# nixie_board.net
KiCad netlist of a schematic drawn in Altium Designer
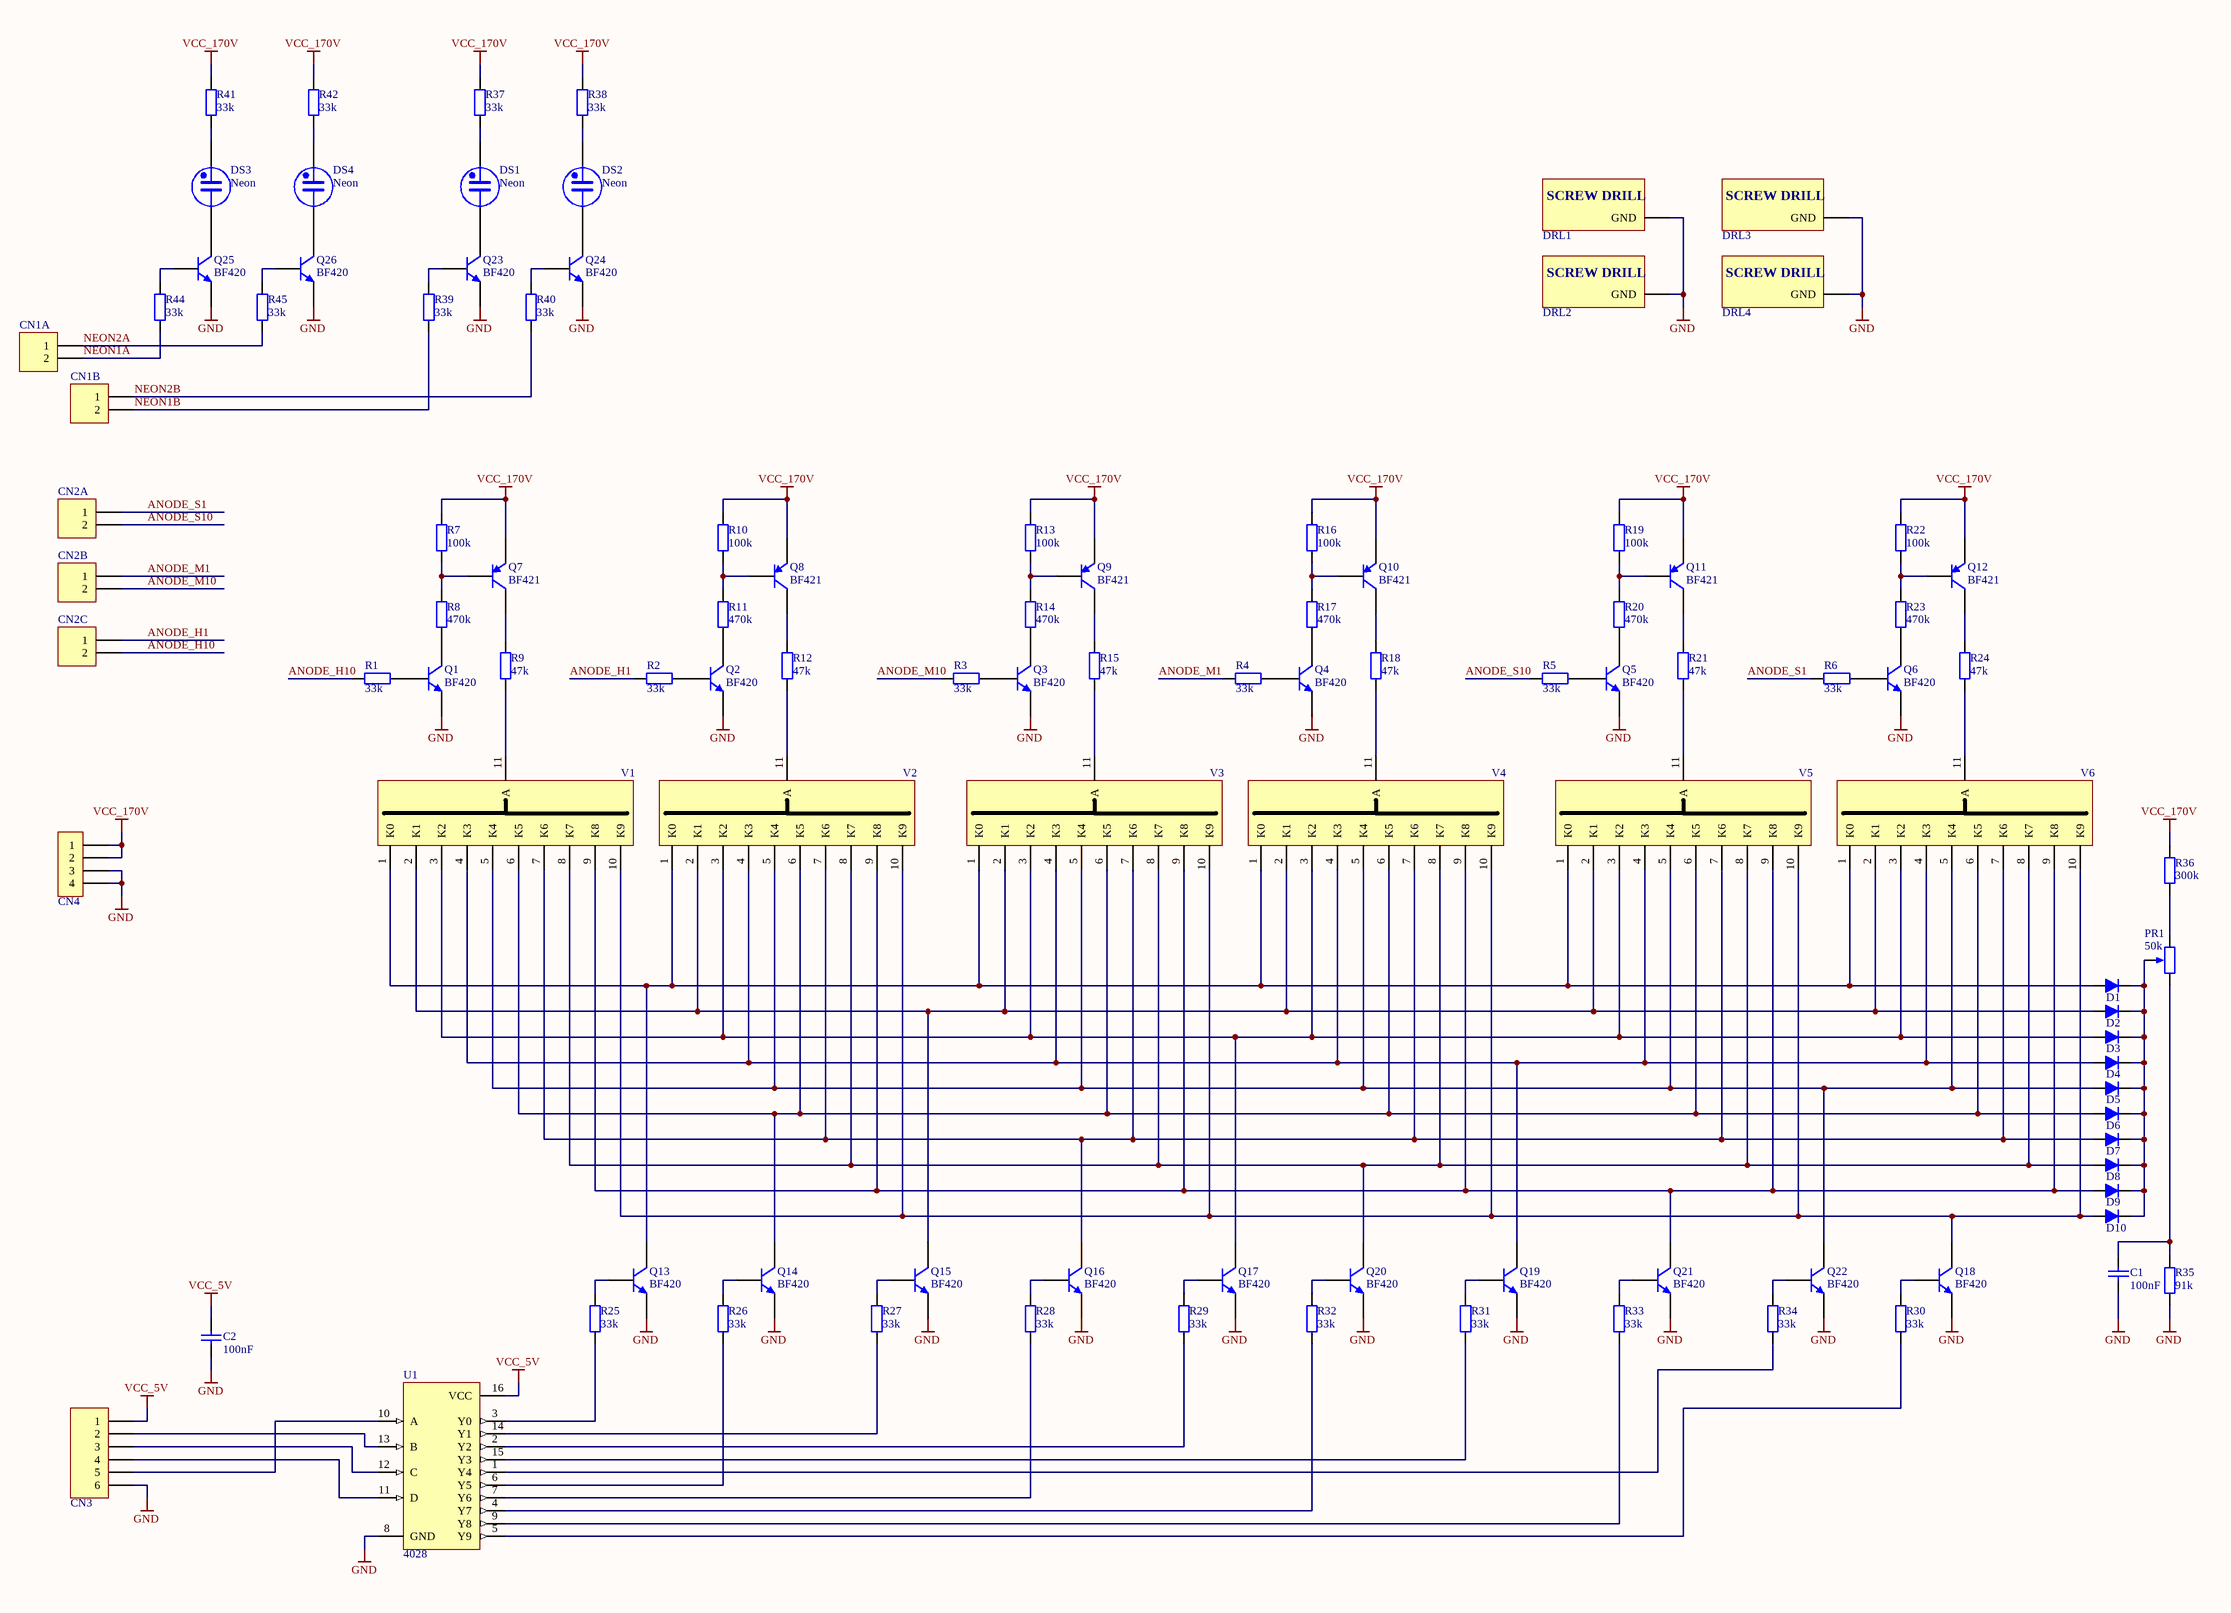
[diagram p0: nixie_board.SCHDOC]

(export (version "E")
  (design (tool "Eeschema 10.0.6"))
  (components
    (comp (ref "C1")
      (value "100nF")
      (footprint "C-RM5")
      (description "Capacitor")
      (libsource (lib "main_lib") (part "Cap"))
    )
    (comp (ref "C2")
      (value "100nF")
      (footprint "C-RM5")
      (description "Capacitor")
      (libsource (lib "main_lib") (part "Cap"))
    )
    (comp (ref "CN1A")
      (value "~")
      (footprint "GP2x1_maual")
      (description "Goldpin, 2-Pin")
      (libsource (lib "main_lib_sch") (part "GP 2X1"))
    )
    (comp (ref "CN1B")
      (value "~")
      (footprint "GP2x1_maual")
      (description "Goldpin, 2-Pin")
      (libsource (lib "main_lib_sch") (part "GP 2X1"))
    )
    (comp (ref "CN2A")
      (value "~")
      (footprint "GP2x1_maual")
      (description "Goldpin, 2-Pin")
      (libsource (lib "main_lib_sch") (part "GP 2X1"))
    )
    (comp (ref "CN2B")
      (value "~")
      (footprint "GP2x1_maual")
      (description "Goldpin, 2-Pin")
      (libsource (lib "main_lib_sch") (part "GP 2X1"))
    )
    (comp (ref "CN2C")
      (value "~")
      (footprint "GP2x1_maual")
      (description "Goldpin, 2-Pin")
      (libsource (lib "main_lib_sch") (part "GP 2X1"))
    )
    (comp (ref "CN3")
      (value "GP 6X1")
      (footprint "GP6x1_manual")
      (description "Gold Pin, 6-Pin")
      (libsource (lib "main_lib") (part "GP 6X1"))
    )
    (comp (ref "CN4")
      (value "~")
      (footprint "GP4x1_MANUAL")
      (description "Gold Pin, 4-Pin")
      (libsource (lib "main_lib_sch") (part "GP 4X1"))
    )
    (comp (ref "D1")
      (value "~")
      (footprint "DO35_LONG")
      (description "Fast rectifier diode: 250V 0.25A, <50ns DO35")
      (libsource (lib "main_lib_sch") (part "BAVP21"))
    )
    (comp (ref "D2")
      (value "~")
      (footprint "DO35_LONG")
      (description "Fast rectifier diode: 250V 0.25A, <50ns DO35")
      (libsource (lib "main_lib_sch") (part "BAVP21"))
    )
    (comp (ref "D3")
      (value "~")
      (footprint "DO35_LONG")
      (description "Fast rectifier diode: 250V 0.25A, <50ns DO35")
      (libsource (lib "main_lib_sch") (part "BAVP21"))
    )
    (comp (ref "D4")
      (value "~")
      (footprint "DO35_LONG")
      (description "Fast rectifier diode: 250V 0.25A, <50ns DO35")
      (libsource (lib "main_lib_sch") (part "BAVP21"))
    )
    (comp (ref "D5")
      (value "~")
      (footprint "DO35_LONG")
      (description "Fast rectifier diode: 250V 0.25A, <50ns DO35")
      (libsource (lib "main_lib_sch") (part "BAVP21"))
    )
    (comp (ref "D6")
      (value "~")
      (footprint "DO35_LONG")
      (description "Fast rectifier diode: 250V 0.25A, <50ns DO35")
      (libsource (lib "main_lib_sch") (part "BAVP21"))
    )
    (comp (ref "D7")
      (value "~")
      (footprint "DO35_LONG")
      (description "Fast rectifier diode: 250V 0.25A, <50ns DO35")
      (libsource (lib "main_lib_sch") (part "BAVP21"))
    )
    (comp (ref "D8")
      (value "~")
      (footprint "DO35_LONG")
      (description "Fast rectifier diode: 250V 0.25A, <50ns DO35")
      (libsource (lib "main_lib_sch") (part "BAVP21"))
    )
    (comp (ref "D9")
      (value "~")
      (footprint "DO35_LONG")
      (description "Fast rectifier diode: 250V 0.25A, <50ns DO35")
      (libsource (lib "main_lib_sch") (part "BAVP21"))
    )
    (comp (ref "D10")
      (value "~")
      (footprint "DO35_LONG")
      (description "Fast rectifier diode: 250V 0.25A, <50ns DO35")
      (libsource (lib "main_lib_sch") (part "BAVP21"))
    )
    (comp (ref "DRL1")
      (value "SCREW DRILL")
      (footprint "3mm screw drill I")
      (description "Screw Drill")
      (libsource (lib "main_lib") (part "SCREW DRILL"))
    )
    (comp (ref "DRL2")
      (value "SCREW DRILL")
      (footprint "3mm screw drill I")
      (description "Screw Drill")
      (libsource (lib "main_lib") (part "SCREW DRILL"))
    )
    (comp (ref "DRL3")
      (value "SCREW DRILL")
      (footprint "3mm screw drill I")
      (description "Screw Drill")
      (libsource (lib "main_lib") (part "SCREW DRILL"))
    )
    (comp (ref "DRL4")
      (value "SCREW DRILL")
      (footprint "3mm screw drill I")
      (description "Screw Drill")
      (libsource (lib "main_lib") (part "SCREW DRILL"))
    )
    (comp (ref "DS1")
      (value "Neon")
      (footprint "NEON_6mm")
      (description "Neon Bulb")
      (fields (field (name "PUBLISHER") "Altium Limited"))
      (libsource (lib "main_lib") (part "Neon"))
    )
    (comp (ref "DS2")
      (value "Neon")
      (footprint "NEON_6mm")
      (description "Neon Bulb")
      (fields (field (name "PUBLISHER") "Altium Limited"))
      (libsource (lib "main_lib") (part "Neon"))
    )
    (comp (ref "DS3")
      (value "Neon")
      (footprint "NEON_6mm")
      (description "Neon Bulb")
      (fields (field (name "PUBLISHER") "Altium Limited"))
      (libsource (lib "main_lib") (part "Neon"))
    )
    (comp (ref "DS4")
      (value "Neon")
      (footprint "NEON_6mm")
      (description "Neon Bulb")
      (fields (field (name "PUBLISHER") "Altium Limited"))
      (libsource (lib "main_lib") (part "Neon"))
    )
    (comp (ref "PR1")
      (value "50k")
      (footprint "CA6V")
      (description "Potentiometer")
      (libsource (lib "main_lib") (part "RPot"))
    )
    (comp (ref "Q1")
      (value "BF420")
      (footprint "TO-92")
      (description "NPN Transistor, 300V, 0.1A, 0.83W")
      (libsource (lib "main_lib_sch") (part "BF420"))
    )
    (comp (ref "Q2")
      (value "BF420")
      (footprint "TO-92")
      (description "NPN Transistor, 300V, 0.1A, 0.83W")
      (libsource (lib "main_lib_sch") (part "BF420"))
    )
    (comp (ref "Q3")
      (value "BF420")
      (footprint "TO-92")
      (description "NPN Transistor, 300V, 0.1A, 0.83W")
      (libsource (lib "main_lib_sch") (part "BF420"))
    )
    (comp (ref "Q4")
      (value "BF420")
      (footprint "TO-92")
      (description "NPN Transistor, 300V, 0.1A, 0.83W")
      (libsource (lib "main_lib_sch") (part "BF420"))
    )
    (comp (ref "Q5")
      (value "BF420")
      (footprint "TO-92")
      (description "NPN Transistor, 300V, 0.1A, 0.83W")
      (libsource (lib "main_lib_sch") (part "BF420"))
    )
    (comp (ref "Q6")
      (value "BF420")
      (footprint "TO-92")
      (description "NPN Transistor, 300V, 0.1A, 0.83W")
      (libsource (lib "main_lib_sch") (part "BF420"))
    )
    (comp (ref "Q7")
      (value "BF421")
      (footprint "TO-92")
      (description "PNP Transistor, 300V, 0.1A, 0.83W")
      (libsource (lib "main_lib_sch") (part "BF421"))
    )
    (comp (ref "Q8")
      (value "BF421")
      (footprint "TO-92")
      (description "PNP Transistor, 300V, 0.1A, 0.83W")
      (libsource (lib "main_lib_sch") (part "BF421"))
    )
    (comp (ref "Q9")
      (value "BF421")
      (footprint "TO-92")
      (description "PNP Transistor, 300V, 0.1A, 0.83W")
      (libsource (lib "main_lib_sch") (part "BF421"))
    )
    (comp (ref "Q10")
      (value "BF421")
      (footprint "TO-92")
      (description "PNP Transistor, 300V, 0.1A, 0.83W")
      (libsource (lib "main_lib_sch") (part "BF421"))
    )
    (comp (ref "Q11")
      (value "BF421")
      (footprint "TO-92")
      (description "PNP Transistor, 300V, 0.1A, 0.83W")
      (libsource (lib "main_lib_sch") (part "BF421"))
    )
    (comp (ref "Q12")
      (value "BF421")
      (footprint "TO-92")
      (description "PNP Transistor, 300V, 0.1A, 0.83W")
      (libsource (lib "main_lib_sch") (part "BF421"))
    )
    (comp (ref "Q13")
      (value "BF420")
      (footprint "TO-92")
      (description "NPN Transistor, 300V, 0.1A, 0.83W")
      (libsource (lib "main_lib_sch") (part "BF420"))
    )
    (comp (ref "Q14")
      (value "BF420")
      (footprint "TO-92")
      (description "NPN Transistor, 300V, 0.1A, 0.83W")
      (libsource (lib "main_lib_sch") (part "BF420"))
    )
    (comp (ref "Q15")
      (value "BF420")
      (footprint "TO-92")
      (description "NPN Transistor, 300V, 0.1A, 0.83W")
      (libsource (lib "main_lib_sch") (part "BF420"))
    )
    (comp (ref "Q16")
      (value "BF420")
      (footprint "TO-92")
      (description "NPN Transistor, 300V, 0.1A, 0.83W")
      (libsource (lib "main_lib_sch") (part "BF420"))
    )
    (comp (ref "Q17")
      (value "BF420")
      (footprint "TO-92")
      (description "NPN Transistor, 300V, 0.1A, 0.83W")
      (libsource (lib "main_lib_sch") (part "BF420"))
    )
    (comp (ref "Q18")
      (value "BF420")
      (footprint "TO-92")
      (description "NPN Transistor, 300V, 0.1A, 0.83W")
      (libsource (lib "main_lib_sch") (part "BF420"))
    )
    (comp (ref "Q19")
      (value "BF420")
      (footprint "TO-92")
      (description "NPN Transistor, 300V, 0.1A, 0.83W")
      (libsource (lib "main_lib_sch") (part "BF420"))
    )
    (comp (ref "Q20")
      (value "BF420")
      (footprint "TO-92")
      (description "NPN Transistor, 300V, 0.1A, 0.83W")
      (libsource (lib "main_lib_sch") (part "BF420"))
    )
    (comp (ref "Q21")
      (value "BF420")
      (footprint "TO-92")
      (description "NPN Transistor, 300V, 0.1A, 0.83W")
      (libsource (lib "main_lib_sch") (part "BF420"))
    )
    (comp (ref "Q22")
      (value "BF420")
      (footprint "TO-92")
      (description "NPN Transistor, 300V, 0.1A, 0.83W")
      (libsource (lib "main_lib_sch") (part "BF420"))
    )
    (comp (ref "Q23")
      (value "BF420")
      (footprint "TO-92")
      (description "NPN Transistor, 300V, 0.1A, 0.83W")
      (libsource (lib "main_lib_sch") (part "BF420"))
    )
    (comp (ref "Q24")
      (value "BF420")
      (footprint "TO-92")
      (description "NPN Transistor, 300V, 0.1A, 0.83W")
      (libsource (lib "main_lib_sch") (part "BF420"))
    )
    (comp (ref "Q25")
      (value "BF420")
      (footprint "TO-92")
      (description "NPN Transistor, 300V, 0.1A, 0.83W")
      (libsource (lib "main_lib_sch") (part "BF420"))
    )
    (comp (ref "Q26")
      (value "BF420")
      (footprint "TO-92")
      (description "NPN Transistor, 300V, 0.1A, 0.83W")
      (libsource (lib "main_lib_sch") (part "BF420"))
    )
    (comp (ref "R1")
      (value "33k")
      (footprint "R10-2")
      (description "Resistor")
      (libsource (lib "") (part "Res_2"))
    )
    (comp (ref "R2")
      (value "33k")
      (footprint "R10-2")
      (description "Resistor")
      (libsource (lib "") (part "Res_2"))
    )
    (comp (ref "R3")
      (value "33k")
      (footprint "R10-2")
      (description "Resistor")
      (libsource (lib "") (part "Res_2"))
    )
    (comp (ref "R4")
      (value "33k")
      (footprint "R10-2")
      (description "Resistor")
      (libsource (lib "") (part "Res_2"))
    )
    (comp (ref "R5")
      (value "33k")
      (footprint "R10-2")
      (description "Resistor")
      (libsource (lib "") (part "Res_2"))
    )
    (comp (ref "R6")
      (value "33k")
      (footprint "R10-2")
      (description "Resistor")
      (libsource (lib "") (part "Res_2"))
    )
    (comp (ref "R7")
      (value "100k")
      (footprint "R10-2")
      (description "Resistor")
      (libsource (lib "") (part "Res_1"))
    )
    (comp (ref "R8")
      (value "470k")
      (footprint "R10-2")
      (description "Resistor")
      (libsource (lib "") (part "Res_1"))
    )
    (comp (ref "R9")
      (value "47k")
      (footprint "R10-2")
      (description "Resistor")
      (libsource (lib "") (part "Res_1"))
    )
    (comp (ref "R10")
      (value "100k")
      (footprint "R10-2")
      (description "Resistor")
      (libsource (lib "") (part "Res_1"))
    )
    (comp (ref "R11")
      (value "470k")
      (footprint "R10-2")
      (description "Resistor")
      (libsource (lib "") (part "Res_1"))
    )
    (comp (ref "R12")
      (value "47k")
      (footprint "R10-2")
      (description "Resistor")
      (libsource (lib "") (part "Res_1"))
    )
    (comp (ref "R13")
      (value "100k")
      (footprint "R10-2")
      (description "Resistor")
      (libsource (lib "") (part "Res_1"))
    )
    (comp (ref "R14")
      (value "470k")
      (footprint "R10-2")
      (description "Resistor")
      (libsource (lib "") (part "Res_1"))
    )
    (comp (ref "R15")
      (value "47k")
      (footprint "R10-2")
      (description "Resistor")
      (libsource (lib "") (part "Res_1"))
    )
    (comp (ref "R16")
      (value "100k")
      (footprint "R10-2")
      (description "Resistor")
      (libsource (lib "") (part "Res_1"))
    )
    (comp (ref "R17")
      (value "470k")
      (footprint "R10-2")
      (description "Resistor")
      (libsource (lib "") (part "Res_1"))
    )
    (comp (ref "R18")
      (value "47k")
      (footprint "R10-2")
      (description "Resistor")
      (libsource (lib "") (part "Res_1"))
    )
    (comp (ref "R19")
      (value "100k")
      (footprint "R10-2")
      (description "Resistor")
      (libsource (lib "") (part "Res_1"))
    )
    (comp (ref "R20")
      (value "470k")
      (footprint "R10-2")
      (description "Resistor")
      (libsource (lib "") (part "Res_1"))
    )
    (comp (ref "R21")
      (value "47k")
      (footprint "R10-2")
      (description "Resistor")
      (libsource (lib "") (part "Res_1"))
    )
    (comp (ref "R22")
      (value "100k")
      (footprint "R10-2")
      (description "Resistor")
      (libsource (lib "") (part "Res_1"))
    )
    (comp (ref "R23")
      (value "470k")
      (footprint "R10-2")
      (description "Resistor")
      (libsource (lib "") (part "Res_1"))
    )
    (comp (ref "R24")
      (value "47k")
      (footprint "R10-2")
      (description "Resistor")
      (libsource (lib "") (part "Res_1"))
    )
    (comp (ref "R25")
      (value "33k")
      (footprint "R10-2")
      (description "Resistor")
      (libsource (lib "") (part "Res_1"))
    )
    (comp (ref "R26")
      (value "33k")
      (footprint "R10-2")
      (description "Resistor")
      (libsource (lib "") (part "Res_1"))
    )
    (comp (ref "R27")
      (value "33k")
      (footprint "R10-2")
      (description "Resistor")
      (libsource (lib "") (part "Res_1"))
    )
    (comp (ref "R28")
      (value "33k")
      (footprint "R10-2")
      (description "Resistor")
      (libsource (lib "") (part "Res_1"))
    )
    (comp (ref "R29")
      (value "33k")
      (footprint "R10-2")
      (description "Resistor")
      (libsource (lib "") (part "Res_1"))
    )
    (comp (ref "R30")
      (value "33k")
      (footprint "R10-2")
      (description "Resistor")
      (libsource (lib "") (part "Res_1"))
    )
    (comp (ref "R31")
      (value "33k")
      (footprint "R10-2")
      (description "Resistor")
      (libsource (lib "") (part "Res_1"))
    )
    (comp (ref "R32")
      (value "33k")
      (footprint "R10-2")
      (description "Resistor")
      (libsource (lib "") (part "Res_1"))
    )
    (comp (ref "R33")
      (value "33k")
      (footprint "R10-2")
      (description "Resistor")
      (libsource (lib "") (part "Res_1"))
    )
    (comp (ref "R34")
      (value "33k")
      (footprint "R10-2")
      (description "Resistor")
      (libsource (lib "") (part "Res_1"))
    )
    (comp (ref "R35")
      (value "91k")
      (footprint "R10-2")
      (description "Resistor")
      (libsource (lib "") (part "Res_1"))
    )
    (comp (ref "R36")
      (value "300k")
      (footprint "R10-2")
      (description "Resistor")
      (libsource (lib "") (part "Res_1"))
    )
    (comp (ref "R37")
      (value "33k")
      (footprint "R10-2")
      (description "Resistor")
      (libsource (lib "") (part "Res_1"))
    )
    (comp (ref "R38")
      (value "33k")
      (footprint "R10-2")
      (description "Resistor")
      (libsource (lib "") (part "Res_1"))
    )
    (comp (ref "R39")
      (value "33k")
      (footprint "R10-2")
      (description "Resistor")
      (libsource (lib "main_lib") (part "Res"))
    )
    (comp (ref "R40")
      (value "33k")
      (footprint "R10-2")
      (description "Resistor")
      (libsource (lib "main_lib") (part "Res"))
    )
    (comp (ref "R41")
      (value "33k")
      (footprint "R10-2")
      (description "Resistor")
      (libsource (lib "") (part "Res_1"))
    )
    (comp (ref "R42")
      (value "33k")
      (footprint "R10-2")
      (description "Resistor")
      (libsource (lib "") (part "Res_1"))
    )
    (comp (ref "R44")
      (value "33k")
      (footprint "R10-2")
      (description "Resistor")
      (libsource (lib "main_lib") (part "Res"))
    )
    (comp (ref "R45")
      (value "33k")
      (footprint "R10-2")
      (description "Resistor")
      (libsource (lib "main_lib") (part "Res"))
    )
    (comp (ref "U1")
      (value "4028")
      (footprint "DIP16_MANUAL")
      (description "BCD-to-Decimal Decoder")
      (fields (field (name "PUBLISHER") "Altium Limited"))
      (libsource (lib "main_lib") (part "4028"))
    )
    (comp (ref "V1")
      (value "Nixie Tube")
      (footprint "LC516_NIXIE_TUBE")
      (description "LC-516 Nixie Tube")
      (libsource (lib "main_lib") (part "LC516"))
    )
    (comp (ref "V2")
      (value "Nixie Tube")
      (footprint "LC516_NIXIE_TUBE")
      (description "LC-516 Nixie Tube")
      (libsource (lib "main_lib") (part "LC516"))
    )
    (comp (ref "V3")
      (value "Nixie Tube")
      (footprint "LC516_NIXIE_TUBE")
      (description "LC-516 Nixie Tube")
      (libsource (lib "main_lib") (part "LC516"))
    )
    (comp (ref "V4")
      (value "Nixie Tube")
      (footprint "LC516_NIXIE_TUBE")
      (description "LC-516 Nixie Tube")
      (libsource (lib "main_lib") (part "LC516"))
    )
    (comp (ref "V5")
      (value "Nixie Tube")
      (footprint "LC516_NIXIE_TUBE")
      (description "LC-516 Nixie Tube")
      (libsource (lib "main_lib") (part "LC516"))
    )
    (comp (ref "V6")
      (value "Nixie Tube")
      (footprint "LC516_NIXIE_TUBE")
      (description "LC-516 Nixie Tube")
      (libsource (lib "main_lib") (part "LC516"))
    )
  )
  (nets
    (net (code "1") (name "/ANODE_H1") (class "Default")
      (node (ref "CN2C") (pin "1") (pinfunction "1_1") (pintype "passive"))
      (node (ref "R2") (pin "1") (pinfunction "1_1") (pintype "passive"))
    )
    (net (code "2") (name "/ANODE_H10") (class "Default")
      (node (ref "CN2C") (pin "2") (pinfunction "2_2") (pintype "passive"))
      (node (ref "R1") (pin "1") (pinfunction "1_1") (pintype "passive"))
    )
    (net (code "3") (name "/ANODE_M1") (class "Default")
      (node (ref "CN2B") (pin "1") (pinfunction "1_1") (pintype "passive"))
      (node (ref "R4") (pin "1") (pinfunction "1_1") (pintype "passive"))
    )
    (net (code "4") (name "/ANODE_M10") (class "Default")
      (node (ref "CN2B") (pin "2") (pinfunction "2_2") (pintype "passive"))
      (node (ref "R3") (pin "1") (pinfunction "1_1") (pintype "passive"))
    )
    (net (code "5") (name "/ANODE_S1") (class "Default")
      (node (ref "CN2A") (pin "1") (pinfunction "1_1") (pintype "passive"))
      (node (ref "R6") (pin "1") (pinfunction "1_1") (pintype "passive"))
    )
    (net (code "6") (name "/ANODE_S10") (class "Default")
      (node (ref "CN2A") (pin "2") (pinfunction "2_2") (pintype "passive"))
      (node (ref "R5") (pin "1") (pinfunction "1_1") (pintype "passive"))
    )
    (net (code "7") (name "/NEON1A") (class "Default")
      (node (ref "CN1A") (pin "2") (pinfunction "2_2") (pintype "passive"))
      (node (ref "R44") (pin "2") (pinfunction "2_2") (pintype "passive"))
    )
    (net (code "8") (name "/NEON1B") (class "Default")
      (node (ref "CN1B") (pin "2") (pinfunction "2_2") (pintype "passive"))
      (node (ref "R39") (pin "2") (pinfunction "2_2") (pintype "passive"))
    )
    (net (code "9") (name "/NEON2A") (class "Default")
      (node (ref "CN1A") (pin "1") (pinfunction "1_1") (pintype "passive"))
      (node (ref "R45") (pin "2") (pinfunction "2_2") (pintype "passive"))
    )
    (net (code "10") (name "/NEON2B") (class "Default")
      (node (ref "CN1B") (pin "1") (pinfunction "1_1") (pintype "passive"))
      (node (ref "R40") (pin "2") (pinfunction "2_2") (pintype "passive"))
    )
    (net (code "11") (name "GND") (class "Default")
      (node (ref "C1") (pin "1") (pinfunction "1_1") (pintype "passive"))
      (node (ref "C2") (pin "1") (pinfunction "1_1") (pintype "passive"))
      (node (ref "CN3") (pin "6") (pinfunction "6_6") (pintype "passive"))
      (node (ref "CN4") (pin "3") (pinfunction "3_3") (pintype "passive"))
      (node (ref "CN4") (pin "4") (pinfunction "4_4") (pintype "passive"))
      (node (ref "DRL1") (pin "0") (pinfunction "GND_0") (pintype "passive"))
      (node (ref "DRL2") (pin "0") (pinfunction "GND_0") (pintype "passive"))
      (node (ref "DRL3") (pin "0") (pinfunction "GND_0") (pintype "passive"))
      (node (ref "DRL4") (pin "0") (pinfunction "GND_0") (pintype "passive"))
      (node (ref "Q1") (pin "1") (pinfunction "E_1") (pintype "passive"))
      (node (ref "Q13") (pin "1") (pinfunction "E_1") (pintype "passive"))
      (node (ref "Q14") (pin "1") (pinfunction "E_1") (pintype "passive"))
      (node (ref "Q15") (pin "1") (pinfunction "E_1") (pintype "passive"))
      (node (ref "Q16") (pin "1") (pinfunction "E_1") (pintype "passive"))
      (node (ref "Q17") (pin "1") (pinfunction "E_1") (pintype "passive"))
      (node (ref "Q18") (pin "1") (pinfunction "E_1") (pintype "passive"))
      (node (ref "Q19") (pin "1") (pinfunction "E_1") (pintype "passive"))
      (node (ref "Q2") (pin "1") (pinfunction "E_1") (pintype "passive"))
      (node (ref "Q20") (pin "1") (pinfunction "E_1") (pintype "passive"))
      (node (ref "Q21") (pin "1") (pinfunction "E_1") (pintype "passive"))
      (node (ref "Q22") (pin "1") (pinfunction "E_1") (pintype "passive"))
      (node (ref "Q23") (pin "1") (pinfunction "E_1") (pintype "passive"))
      (node (ref "Q24") (pin "1") (pinfunction "E_1") (pintype "passive"))
      (node (ref "Q25") (pin "1") (pinfunction "E_1") (pintype "passive"))
      (node (ref "Q26") (pin "1") (pinfunction "E_1") (pintype "passive"))
      (node (ref "Q3") (pin "1") (pinfunction "E_1") (pintype "passive"))
      (node (ref "Q4") (pin "1") (pinfunction "E_1") (pintype "passive"))
      (node (ref "Q5") (pin "1") (pinfunction "E_1") (pintype "passive"))
      (node (ref "Q6") (pin "1") (pinfunction "E_1") (pintype "passive"))
      (node (ref "R35") (pin "1") (pinfunction "1_1") (pintype "passive"))
      (node (ref "U1") (pin "8") (pinfunction "GND_8") (pintype "power_in"))
    )
    (net (code "12") (name "Net-(D1-A)") (class "Default")
      (node (ref "D1") (pin "1") (pinfunction "A_1") (pintype "passive"))
      (node (ref "Q13") (pin "2") (pinfunction "C_2") (pintype "passive"))
      (node (ref "V1") (pin "1") (pinfunction "K0_1") (pintype "passive"))
      (node (ref "V2") (pin "1") (pinfunction "K0_1") (pintype "passive"))
      (node (ref "V3") (pin "1") (pinfunction "K0_1") (pintype "passive"))
      (node (ref "V4") (pin "1") (pinfunction "K0_1") (pintype "passive"))
      (node (ref "V5") (pin "1") (pinfunction "K0_1") (pintype "passive"))
      (node (ref "V6") (pin "1") (pinfunction "K0_1") (pintype "passive"))
    )
    (net (code "13") (name "Net-(D1-K)") (class "Default")
      (node (ref "D1") (pin "2") (pinfunction "K_2") (pintype "passive"))
      (node (ref "D10") (pin "2") (pinfunction "K_2") (pintype "passive"))
      (node (ref "D2") (pin "2") (pinfunction "K_2") (pintype "passive"))
      (node (ref "D3") (pin "2") (pinfunction "K_2") (pintype "passive"))
      (node (ref "D4") (pin "2") (pinfunction "K_2") (pintype "passive"))
      (node (ref "D5") (pin "2") (pinfunction "K_2") (pintype "passive"))
      (node (ref "D6") (pin "2") (pinfunction "K_2") (pintype "passive"))
      (node (ref "D7") (pin "2") (pinfunction "K_2") (pintype "passive"))
      (node (ref "D8") (pin "2") (pinfunction "K_2") (pintype "passive"))
      (node (ref "D9") (pin "2") (pinfunction "K_2") (pintype "passive"))
      (node (ref "PR1") (pin "3") (pinfunction "TAP_3") (pintype "passive"))
    )
    (net (code "14") (name "Net-(D2-A)") (class "Default")
      (node (ref "D2") (pin "1") (pinfunction "A_1") (pintype "passive"))
      (node (ref "Q15") (pin "2") (pinfunction "C_2") (pintype "passive"))
      (node (ref "V1") (pin "2") (pinfunction "K1_2") (pintype "passive"))
      (node (ref "V2") (pin "2") (pinfunction "K1_2") (pintype "passive"))
      (node (ref "V3") (pin "2") (pinfunction "K1_2") (pintype "passive"))
      (node (ref "V4") (pin "2") (pinfunction "K1_2") (pintype "passive"))
      (node (ref "V5") (pin "2") (pinfunction "K1_2") (pintype "passive"))
      (node (ref "V6") (pin "2") (pinfunction "K1_2") (pintype "passive"))
    )
    (net (code "15") (name "Net-(D3-A)") (class "Default")
      (node (ref "D3") (pin "1") (pinfunction "A_1") (pintype "passive"))
      (node (ref "Q17") (pin "2") (pinfunction "C_2") (pintype "passive"))
      (node (ref "V1") (pin "3") (pinfunction "K2_3") (pintype "passive"))
      (node (ref "V2") (pin "3") (pinfunction "K2_3") (pintype "passive"))
      (node (ref "V3") (pin "3") (pinfunction "K2_3") (pintype "passive"))
      (node (ref "V4") (pin "3") (pinfunction "K2_3") (pintype "passive"))
      (node (ref "V5") (pin "3") (pinfunction "K2_3") (pintype "passive"))
      (node (ref "V6") (pin "3") (pinfunction "K2_3") (pintype "passive"))
    )
    (net (code "16") (name "Net-(D4-A)") (class "Default")
      (node (ref "D4") (pin "1") (pinfunction "A_1") (pintype "passive"))
      (node (ref "Q19") (pin "2") (pinfunction "C_2") (pintype "passive"))
      (node (ref "V1") (pin "4") (pinfunction "K3_4") (pintype "passive"))
      (node (ref "V2") (pin "4") (pinfunction "K3_4") (pintype "passive"))
      (node (ref "V3") (pin "4") (pinfunction "K3_4") (pintype "passive"))
      (node (ref "V4") (pin "4") (pinfunction "K3_4") (pintype "passive"))
      (node (ref "V5") (pin "4") (pinfunction "K3_4") (pintype "passive"))
      (node (ref "V6") (pin "4") (pinfunction "K3_4") (pintype "passive"))
    )
    (net (code "17") (name "Net-(D5-A)") (class "Default")
      (node (ref "D5") (pin "1") (pinfunction "A_1") (pintype "passive"))
      (node (ref "Q22") (pin "2") (pinfunction "C_2") (pintype "passive"))
      (node (ref "V1") (pin "5") (pinfunction "K4_5") (pintype "passive"))
      (node (ref "V2") (pin "5") (pinfunction "K4_5") (pintype "passive"))
      (node (ref "V3") (pin "5") (pinfunction "K4_5") (pintype "passive"))
      (node (ref "V4") (pin "5") (pinfunction "K4_5") (pintype "passive"))
      (node (ref "V5") (pin "5") (pinfunction "K4_5") (pintype "passive"))
      (node (ref "V6") (pin "5") (pinfunction "K4_5") (pintype "passive"))
    )
    (net (code "18") (name "Net-(D6-A)") (class "Default")
      (node (ref "D6") (pin "1") (pinfunction "A_1") (pintype "passive"))
      (node (ref "Q14") (pin "2") (pinfunction "C_2") (pintype "passive"))
      (node (ref "V1") (pin "6") (pinfunction "K5_6") (pintype "passive"))
      (node (ref "V2") (pin "6") (pinfunction "K5_6") (pintype "passive"))
      (node (ref "V3") (pin "6") (pinfunction "K5_6") (pintype "passive"))
      (node (ref "V4") (pin "6") (pinfunction "K5_6") (pintype "passive"))
      (node (ref "V5") (pin "6") (pinfunction "K5_6") (pintype "passive"))
      (node (ref "V6") (pin "6") (pinfunction "K5_6") (pintype "passive"))
    )
    (net (code "19") (name "Net-(D7-A)") (class "Default")
      (node (ref "D7") (pin "1") (pinfunction "A_1") (pintype "passive"))
      (node (ref "Q16") (pin "2") (pinfunction "C_2") (pintype "passive"))
      (node (ref "V1") (pin "7") (pinfunction "K6_7") (pintype "passive"))
      (node (ref "V2") (pin "7") (pinfunction "K6_7") (pintype "passive"))
      (node (ref "V3") (pin "7") (pinfunction "K6_7") (pintype "passive"))
      (node (ref "V4") (pin "7") (pinfunction "K6_7") (pintype "passive"))
      (node (ref "V5") (pin "7") (pinfunction "K6_7") (pintype "passive"))
      (node (ref "V6") (pin "7") (pinfunction "K6_7") (pintype "passive"))
    )
    (net (code "20") (name "Net-(D8-A)") (class "Default")
      (node (ref "D8") (pin "1") (pinfunction "A_1") (pintype "passive"))
      (node (ref "Q20") (pin "2") (pinfunction "C_2") (pintype "passive"))
      (node (ref "V1") (pin "8") (pinfunction "K7_8") (pintype "passive"))
      (node (ref "V2") (pin "8") (pinfunction "K7_8") (pintype "passive"))
      (node (ref "V3") (pin "8") (pinfunction "K7_8") (pintype "passive"))
      (node (ref "V4") (pin "8") (pinfunction "K7_8") (pintype "passive"))
      (node (ref "V5") (pin "8") (pinfunction "K7_8") (pintype "passive"))
      (node (ref "V6") (pin "8") (pinfunction "K7_8") (pintype "passive"))
    )
    (net (code "21") (name "Net-(D9-A)") (class "Default")
      (node (ref "D9") (pin "1") (pinfunction "A_1") (pintype "passive"))
      (node (ref "Q21") (pin "2") (pinfunction "C_2") (pintype "passive"))
      (node (ref "V1") (pin "9") (pinfunction "K8_9") (pintype "passive"))
      (node (ref "V2") (pin "9") (pinfunction "K8_9") (pintype "passive"))
      (node (ref "V3") (pin "9") (pinfunction "K8_9") (pintype "passive"))
      (node (ref "V4") (pin "9") (pinfunction "K8_9") (pintype "passive"))
      (node (ref "V5") (pin "9") (pinfunction "K8_9") (pintype "passive"))
      (node (ref "V6") (pin "9") (pinfunction "K8_9") (pintype "passive"))
    )
    (net (code "22") (name "Net-(D10-A)") (class "Default")
      (node (ref "D10") (pin "1") (pinfunction "A_1") (pintype "passive"))
      (node (ref "Q18") (pin "2") (pinfunction "C_2") (pintype "passive"))
      (node (ref "V1") (pin "10") (pinfunction "K9_10") (pintype "passive"))
      (node (ref "V2") (pin "10") (pinfunction "K9_10") (pintype "passive"))
      (node (ref "V3") (pin "10") (pinfunction "K9_10") (pintype "passive"))
      (node (ref "V4") (pin "10") (pinfunction "K9_10") (pintype "passive"))
      (node (ref "V5") (pin "10") (pinfunction "K9_10") (pintype "passive"))
      (node (ref "V6") (pin "10") (pinfunction "K9_10") (pintype "passive"))
    )
    (net (code "23") (name "Net-(DS1-Pad1)") (class "Default")
      (node (ref "DS1") (pin "1") (pinfunction "1_1") (pintype "passive"))
      (node (ref "R37") (pin "1") (pinfunction "1_1") (pintype "passive"))
    )
    (net (code "24") (name "Net-(DS2-Pad1)") (class "Default")
      (node (ref "DS2") (pin "1") (pinfunction "1_1") (pintype "passive"))
      (node (ref "R38") (pin "1") (pinfunction "1_1") (pintype "passive"))
    )
    (net (code "25") (name "Net-(DS3-Pad1)") (class "Default")
      (node (ref "DS3") (pin "1") (pinfunction "1_1") (pintype "passive"))
      (node (ref "R41") (pin "1") (pinfunction "1_1") (pintype "passive"))
    )
    (net (code "26") (name "Net-(DS4-Pad1)") (class "Default")
      (node (ref "DS4") (pin "1") (pinfunction "1_1") (pintype "passive"))
      (node (ref "R42") (pin "1") (pinfunction "1_1") (pintype "passive"))
    )
    (net (code "27") (name "Net-(PR1-BOT)") (class "Default")
      (node (ref "C1") (pin "2") (pinfunction "2_2") (pintype "passive"))
      (node (ref "PR1") (pin "2") (pinfunction "BOT_2") (pintype "passive"))
      (node (ref "R35") (pin "2") (pinfunction "2_2") (pintype "passive"))
    )
    (net (code "28") (name "Net-(PR1-TOP)") (class "Default")
      (node (ref "PR1") (pin "1") (pinfunction "TOP_1") (pintype "passive"))
      (node (ref "R36") (pin "1") (pinfunction "1_1") (pintype "passive"))
    )
    (net (code "29") (name "Net-(Q1-B)") (class "Default")
      (node (ref "Q1") (pin "3") (pinfunction "B_3") (pintype "passive"))
      (node (ref "R1") (pin "2") (pinfunction "2_2") (pintype "passive"))
    )
    (net (code "30") (name "Net-(Q1-C)") (class "Default")
      (node (ref "Q1") (pin "2") (pinfunction "C_2") (pintype "passive"))
      (node (ref "R8") (pin "1") (pinfunction "1_1") (pintype "passive"))
    )
    (net (code "31") (name "Net-(Q2-B)") (class "Default")
      (node (ref "Q2") (pin "3") (pinfunction "B_3") (pintype "passive"))
      (node (ref "R2") (pin "2") (pinfunction "2_2") (pintype "passive"))
    )
    (net (code "32") (name "Net-(Q2-C)") (class "Default")
      (node (ref "Q2") (pin "2") (pinfunction "C_2") (pintype "passive"))
      (node (ref "R11") (pin "1") (pinfunction "1_1") (pintype "passive"))
    )
    (net (code "33") (name "Net-(Q3-B)") (class "Default")
      (node (ref "Q3") (pin "3") (pinfunction "B_3") (pintype "passive"))
      (node (ref "R3") (pin "2") (pinfunction "2_2") (pintype "passive"))
    )
    (net (code "34") (name "Net-(Q3-C)") (class "Default")
      (node (ref "Q3") (pin "2") (pinfunction "C_2") (pintype "passive"))
      (node (ref "R14") (pin "1") (pinfunction "1_1") (pintype "passive"))
    )
    (net (code "35") (name "Net-(Q4-B)") (class "Default")
      (node (ref "Q4") (pin "3") (pinfunction "B_3") (pintype "passive"))
      (node (ref "R4") (pin "2") (pinfunction "2_2") (pintype "passive"))
    )
    (net (code "36") (name "Net-(Q4-C)") (class "Default")
      (node (ref "Q4") (pin "2") (pinfunction "C_2") (pintype "passive"))
      (node (ref "R17") (pin "1") (pinfunction "1_1") (pintype "passive"))
    )
    (net (code "37") (name "Net-(Q5-B)") (class "Default")
      (node (ref "Q5") (pin "3") (pinfunction "B_3") (pintype "passive"))
      (node (ref "R5") (pin "2") (pinfunction "2_2") (pintype "passive"))
    )
    (net (code "38") (name "Net-(Q5-C)") (class "Default")
      (node (ref "Q5") (pin "2") (pinfunction "C_2") (pintype "passive"))
      (node (ref "R20") (pin "1") (pinfunction "1_1") (pintype "passive"))
    )
    (net (code "39") (name "Net-(Q6-B)") (class "Default")
      (node (ref "Q6") (pin "3") (pinfunction "B_3") (pintype "passive"))
      (node (ref "R6") (pin "2") (pinfunction "2_2") (pintype "passive"))
    )
    (net (code "40") (name "Net-(Q6-C)") (class "Default")
      (node (ref "Q6") (pin "2") (pinfunction "C_2") (pintype "passive"))
      (node (ref "R23") (pin "1") (pinfunction "1_1") (pintype "passive"))
    )
    (net (code "41") (name "Net-(Q7-B)") (class "Default")
      (node (ref "Q7") (pin "3") (pinfunction "B_3") (pintype "passive"))
      (node (ref "R7") (pin "1") (pinfunction "1_1") (pintype "passive"))
      (node (ref "R8") (pin "2") (pinfunction "2_2") (pintype "passive"))
    )
    (net (code "42") (name "Net-(Q7-C)") (class "Default")
      (node (ref "Q7") (pin "2") (pinfunction "C_2") (pintype "passive"))
      (node (ref "R9") (pin "2") (pinfunction "2_2") (pintype "passive"))
    )
    (net (code "43") (name "Net-(Q8-B)") (class "Default")
      (node (ref "Q8") (pin "3") (pinfunction "B_3") (pintype "passive"))
      (node (ref "R10") (pin "1") (pinfunction "1_1") (pintype "passive"))
      (node (ref "R11") (pin "2") (pinfunction "2_2") (pintype "passive"))
    )
    (net (code "44") (name "Net-(Q8-C)") (class "Default")
      (node (ref "Q8") (pin "2") (pinfunction "C_2") (pintype "passive"))
      (node (ref "R12") (pin "2") (pinfunction "2_2") (pintype "passive"))
    )
    (net (code "45") (name "Net-(Q9-B)") (class "Default")
      (node (ref "Q9") (pin "3") (pinfunction "B_3") (pintype "passive"))
      (node (ref "R13") (pin "1") (pinfunction "1_1") (pintype "passive"))
      (node (ref "R14") (pin "2") (pinfunction "2_2") (pintype "passive"))
    )
    (net (code "46") (name "Net-(Q9-C)") (class "Default")
      (node (ref "Q9") (pin "2") (pinfunction "C_2") (pintype "passive"))
      (node (ref "R15") (pin "2") (pinfunction "2_2") (pintype "passive"))
    )
    (net (code "47") (name "Net-(Q10-B)") (class "Default")
      (node (ref "Q10") (pin "3") (pinfunction "B_3") (pintype "passive"))
      (node (ref "R16") (pin "1") (pinfunction "1_1") (pintype "passive"))
      (node (ref "R17") (pin "2") (pinfunction "2_2") (pintype "passive"))
    )
    (net (code "48") (name "Net-(Q10-C)") (class "Default")
      (node (ref "Q10") (pin "2") (pinfunction "C_2") (pintype "passive"))
      (node (ref "R18") (pin "2") (pinfunction "2_2") (pintype "passive"))
    )
    (net (code "49") (name "Net-(Q11-B)") (class "Default")
      (node (ref "Q11") (pin "3") (pinfunction "B_3") (pintype "passive"))
      (node (ref "R19") (pin "1") (pinfunction "1_1") (pintype "passive"))
      (node (ref "R20") (pin "2") (pinfunction "2_2") (pintype "passive"))
    )
    (net (code "50") (name "Net-(Q11-C)") (class "Default")
      (node (ref "Q11") (pin "2") (pinfunction "C_2") (pintype "passive"))
      (node (ref "R21") (pin "2") (pinfunction "2_2") (pintype "passive"))
    )
    (net (code "51") (name "Net-(Q12-B)") (class "Default")
      (node (ref "Q12") (pin "3") (pinfunction "B_3") (pintype "passive"))
      (node (ref "R22") (pin "1") (pinfunction "1_1") (pintype "passive"))
      (node (ref "R23") (pin "2") (pinfunction "2_2") (pintype "passive"))
    )
    (net (code "52") (name "Net-(Q12-C)") (class "Default")
      (node (ref "Q12") (pin "2") (pinfunction "C_2") (pintype "passive"))
      (node (ref "R24") (pin "2") (pinfunction "2_2") (pintype "passive"))
    )
    (net (code "53") (name "Net-(Q13-B)") (class "Default")
      (node (ref "Q13") (pin "3") (pinfunction "B_3") (pintype "passive"))
      (node (ref "R25") (pin "2") (pinfunction "2_2") (pintype "passive"))
    )
    (net (code "54") (name "Net-(Q14-B)") (class "Default")
      (node (ref "Q14") (pin "3") (pinfunction "B_3") (pintype "passive"))
      (node (ref "R26") (pin "2") (pinfunction "2_2") (pintype "passive"))
    )
    (net (code "55") (name "Net-(Q15-B)") (class "Default")
      (node (ref "Q15") (pin "3") (pinfunction "B_3") (pintype "passive"))
      (node (ref "R27") (pin "2") (pinfunction "2_2") (pintype "passive"))
    )
    (net (code "56") (name "Net-(Q16-B)") (class "Default")
      (node (ref "Q16") (pin "3") (pinfunction "B_3") (pintype "passive"))
      (node (ref "R28") (pin "2") (pinfunction "2_2") (pintype "passive"))
    )
    (net (code "57") (name "Net-(Q17-B)") (class "Default")
      (node (ref "Q17") (pin "3") (pinfunction "B_3") (pintype "passive"))
      (node (ref "R29") (pin "2") (pinfunction "2_2") (pintype "passive"))
    )
    (net (code "58") (name "Net-(Q18-B)") (class "Default")
      (node (ref "Q18") (pin "3") (pinfunction "B_3") (pintype "passive"))
      (node (ref "R30") (pin "2") (pinfunction "2_2") (pintype "passive"))
    )
    (net (code "59") (name "Net-(Q19-B)") (class "Default")
      (node (ref "Q19") (pin "3") (pinfunction "B_3") (pintype "passive"))
      (node (ref "R31") (pin "2") (pinfunction "2_2") (pintype "passive"))
    )
    (net (code "60") (name "Net-(Q20-B)") (class "Default")
      (node (ref "Q20") (pin "3") (pinfunction "B_3") (pintype "passive"))
      (node (ref "R32") (pin "2") (pinfunction "2_2") (pintype "passive"))
    )
    (net (code "61") (name "Net-(Q21-B)") (class "Default")
      (node (ref "Q21") (pin "3") (pinfunction "B_3") (pintype "passive"))
      (node (ref "R33") (pin "2") (pinfunction "2_2") (pintype "passive"))
    )
    (net (code "62") (name "Net-(Q22-B)") (class "Default")
      (node (ref "Q22") (pin "3") (pinfunction "B_3") (pintype "passive"))
      (node (ref "R34") (pin "2") (pinfunction "2_2") (pintype "passive"))
    )
    (net (code "63") (name "Net-(Q23-B)") (class "Default")
      (node (ref "Q23") (pin "3") (pinfunction "B_3") (pintype "passive"))
      (node (ref "R39") (pin "1") (pinfunction "1_1") (pintype "passive"))
    )
    (net (code "64") (name "Net-(Q23-C)") (class "Default")
      (node (ref "DS1") (pin "2") (pinfunction "2_2") (pintype "passive"))
      (node (ref "Q23") (pin "2") (pinfunction "C_2") (pintype "passive"))
    )
    (net (code "65") (name "Net-(Q24-B)") (class "Default")
      (node (ref "Q24") (pin "3") (pinfunction "B_3") (pintype "passive"))
      (node (ref "R40") (pin "1") (pinfunction "1_1") (pintype "passive"))
    )
    (net (code "66") (name "Net-(Q24-C)") (class "Default")
      (node (ref "DS2") (pin "2") (pinfunction "2_2") (pintype "passive"))
      (node (ref "Q24") (pin "2") (pinfunction "C_2") (pintype "passive"))
    )
    (net (code "67") (name "Net-(Q25-B)") (class "Default")
      (node (ref "Q25") (pin "3") (pinfunction "B_3") (pintype "passive"))
      (node (ref "R44") (pin "1") (pinfunction "1_1") (pintype "passive"))
    )
    (net (code "68") (name "Net-(Q25-C)") (class "Default")
      (node (ref "DS3") (pin "2") (pinfunction "2_2") (pintype "passive"))
      (node (ref "Q25") (pin "2") (pinfunction "C_2") (pintype "passive"))
    )
    (net (code "69") (name "Net-(Q26-B)") (class "Default")
      (node (ref "Q26") (pin "3") (pinfunction "B_3") (pintype "passive"))
      (node (ref "R45") (pin "1") (pinfunction "1_1") (pintype "passive"))
    )
    (net (code "70") (name "Net-(Q26-C)") (class "Default")
      (node (ref "DS4") (pin "2") (pinfunction "2_2") (pintype "passive"))
      (node (ref "Q26") (pin "2") (pinfunction "C_2") (pintype "passive"))
    )
    (net (code "71") (name "Net-(U1-A)") (class "Default")
      (node (ref "CN3") (pin "5") (pinfunction "5_5") (pintype "passive"))
      (node (ref "U1") (pin "10") (pinfunction "A_10") (pintype "input"))
    )
    (net (code "72") (name "Net-(U1-B)") (class "Default")
      (node (ref "CN3") (pin "2") (pinfunction "2_2") (pintype "passive"))
      (node (ref "U1") (pin "13") (pinfunction "B_13") (pintype "input"))
    )
    (net (code "73") (name "Net-(U1-C)") (class "Default")
      (node (ref "CN3") (pin "3") (pinfunction "3_3") (pintype "passive"))
      (node (ref "U1") (pin "12") (pinfunction "C_12") (pintype "input"))
    )
    (net (code "74") (name "Net-(U1-D)") (class "Default")
      (node (ref "CN3") (pin "4") (pinfunction "4_4") (pintype "passive"))
      (node (ref "U1") (pin "11") (pinfunction "D_11") (pintype "input"))
    )
    (net (code "75") (name "Net-(U1-Y0)") (class "Default")
      (node (ref "R25") (pin "1") (pinfunction "1_1") (pintype "passive"))
      (node (ref "U1") (pin "3") (pinfunction "Y0_3") (pintype "output"))
    )
    (net (code "76") (name "Net-(U1-Y1)") (class "Default")
      (node (ref "R27") (pin "1") (pinfunction "1_1") (pintype "passive"))
      (node (ref "U1") (pin "14") (pinfunction "Y1_14") (pintype "output"))
    )
    (net (code "77") (name "Net-(U1-Y2)") (class "Default")
      (node (ref "R29") (pin "1") (pinfunction "1_1") (pintype "passive"))
      (node (ref "U1") (pin "2") (pinfunction "Y2_2") (pintype "output"))
    )
    (net (code "78") (name "Net-(U1-Y3)") (class "Default")
      (node (ref "R31") (pin "1") (pinfunction "1_1") (pintype "passive"))
      (node (ref "U1") (pin "15") (pinfunction "Y3_15") (pintype "output"))
    )
    (net (code "79") (name "Net-(U1-Y4)") (class "Default")
      (node (ref "R34") (pin "1") (pinfunction "1_1") (pintype "passive"))
      (node (ref "U1") (pin "1") (pinfunction "Y4_1") (pintype "output"))
    )
    (net (code "80") (name "Net-(U1-Y5)") (class "Default")
      (node (ref "R26") (pin "1") (pinfunction "1_1") (pintype "passive"))
      (node (ref "U1") (pin "6") (pinfunction "Y5_6") (pintype "output"))
    )
    (net (code "81") (name "Net-(U1-Y6)") (class "Default")
      (node (ref "R28") (pin "1") (pinfunction "1_1") (pintype "passive"))
      (node (ref "U1") (pin "7") (pinfunction "Y6_7") (pintype "output"))
    )
    (net (code "82") (name "Net-(U1-Y7)") (class "Default")
      (node (ref "R32") (pin "1") (pinfunction "1_1") (pintype "passive"))
      (node (ref "U1") (pin "4") (pinfunction "Y7_4") (pintype "output"))
    )
    (net (code "83") (name "Net-(U1-Y8)") (class "Default")
      (node (ref "R33") (pin "1") (pinfunction "1_1") (pintype "passive"))
      (node (ref "U1") (pin "9") (pinfunction "Y8_9") (pintype "output"))
    )
    (net (code "84") (name "Net-(U1-Y9)") (class "Default")
      (node (ref "R30") (pin "1") (pinfunction "1_1") (pintype "passive"))
      (node (ref "U1") (pin "5") (pinfunction "Y9_5") (pintype "output"))
    )
    (net (code "85") (name "Net-(V1-A)") (class "Default")
      (node (ref "R9") (pin "1") (pinfunction "1_1") (pintype "passive"))
      (node (ref "V1") (pin "11") (pinfunction "A_11") (pintype "passive"))
    )
    (net (code "86") (name "Net-(V2-A)") (class "Default")
      (node (ref "R12") (pin "1") (pinfunction "1_1") (pintype "passive"))
      (node (ref "V2") (pin "11") (pinfunction "A_11") (pintype "passive"))
    )
    (net (code "87") (name "Net-(V3-A)") (class "Default")
      (node (ref "R15") (pin "1") (pinfunction "1_1") (pintype "passive"))
      (node (ref "V3") (pin "11") (pinfunction "A_11") (pintype "passive"))
    )
    (net (code "88") (name "Net-(V4-A)") (class "Default")
      (node (ref "R18") (pin "1") (pinfunction "1_1") (pintype "passive"))
      (node (ref "V4") (pin "11") (pinfunction "A_11") (pintype "passive"))
    )
    (net (code "89") (name "Net-(V5-A)") (class "Default")
      (node (ref "R21") (pin "1") (pinfunction "1_1") (pintype "passive"))
      (node (ref "V5") (pin "11") (pinfunction "A_11") (pintype "passive"))
    )
    (net (code "90") (name "Net-(V6-A)") (class "Default")
      (node (ref "R24") (pin "1") (pinfunction "1_1") (pintype "passive"))
      (node (ref "V6") (pin "11") (pinfunction "A_11") (pintype "passive"))
    )
    (net (code "91") (name "VCC_5V") (class "Default")
      (node (ref "C2") (pin "2") (pinfunction "2_2") (pintype "passive"))
      (node (ref "CN3") (pin "1") (pinfunction "1_1") (pintype "passive"))
      (node (ref "U1") (pin "16") (pinfunction "VCC_16") (pintype "power_in"))
    )
    (net (code "92") (name "VCC_170V") (class "Default")
      (node (ref "CN4") (pin "1") (pinfunction "1_1") (pintype "passive"))
      (node (ref "CN4") (pin "2") (pinfunction "2_2") (pintype "passive"))
      (node (ref "Q10") (pin "1") (pinfunction "E_1") (pintype "passive"))
      (node (ref "Q11") (pin "1") (pinfunction "E_1") (pintype "passive"))
      (node (ref "Q12") (pin "1") (pinfunction "E_1") (pintype "passive"))
      (node (ref "Q7") (pin "1") (pinfunction "E_1") (pintype "passive"))
      (node (ref "Q8") (pin "1") (pinfunction "E_1") (pintype "passive"))
      (node (ref "Q9") (pin "1") (pinfunction "E_1") (pintype "passive"))
      (node (ref "R10") (pin "2") (pinfunction "2_2") (pintype "passive"))
      (node (ref "R13") (pin "2") (pinfunction "2_2") (pintype "passive"))
      (node (ref "R16") (pin "2") (pinfunction "2_2") (pintype "passive"))
      (node (ref "R19") (pin "2") (pinfunction "2_2") (pintype "passive"))
      (node (ref "R22") (pin "2") (pinfunction "2_2") (pintype "passive"))
      (node (ref "R36") (pin "2") (pinfunction "2_2") (pintype "passive"))
      (node (ref "R37") (pin "2") (pinfunction "2_2") (pintype "passive"))
      (node (ref "R38") (pin "2") (pinfunction "2_2") (pintype "passive"))
      (node (ref "R41") (pin "2") (pinfunction "2_2") (pintype "passive"))
      (node (ref "R42") (pin "2") (pinfunction "2_2") (pintype "passive"))
      (node (ref "R7") (pin "2") (pinfunction "2_2") (pintype "passive"))
    )
  )
)
